# esp32-hanover-flipdot.net
KiCad netlist of a schematic drawn in EAGLE
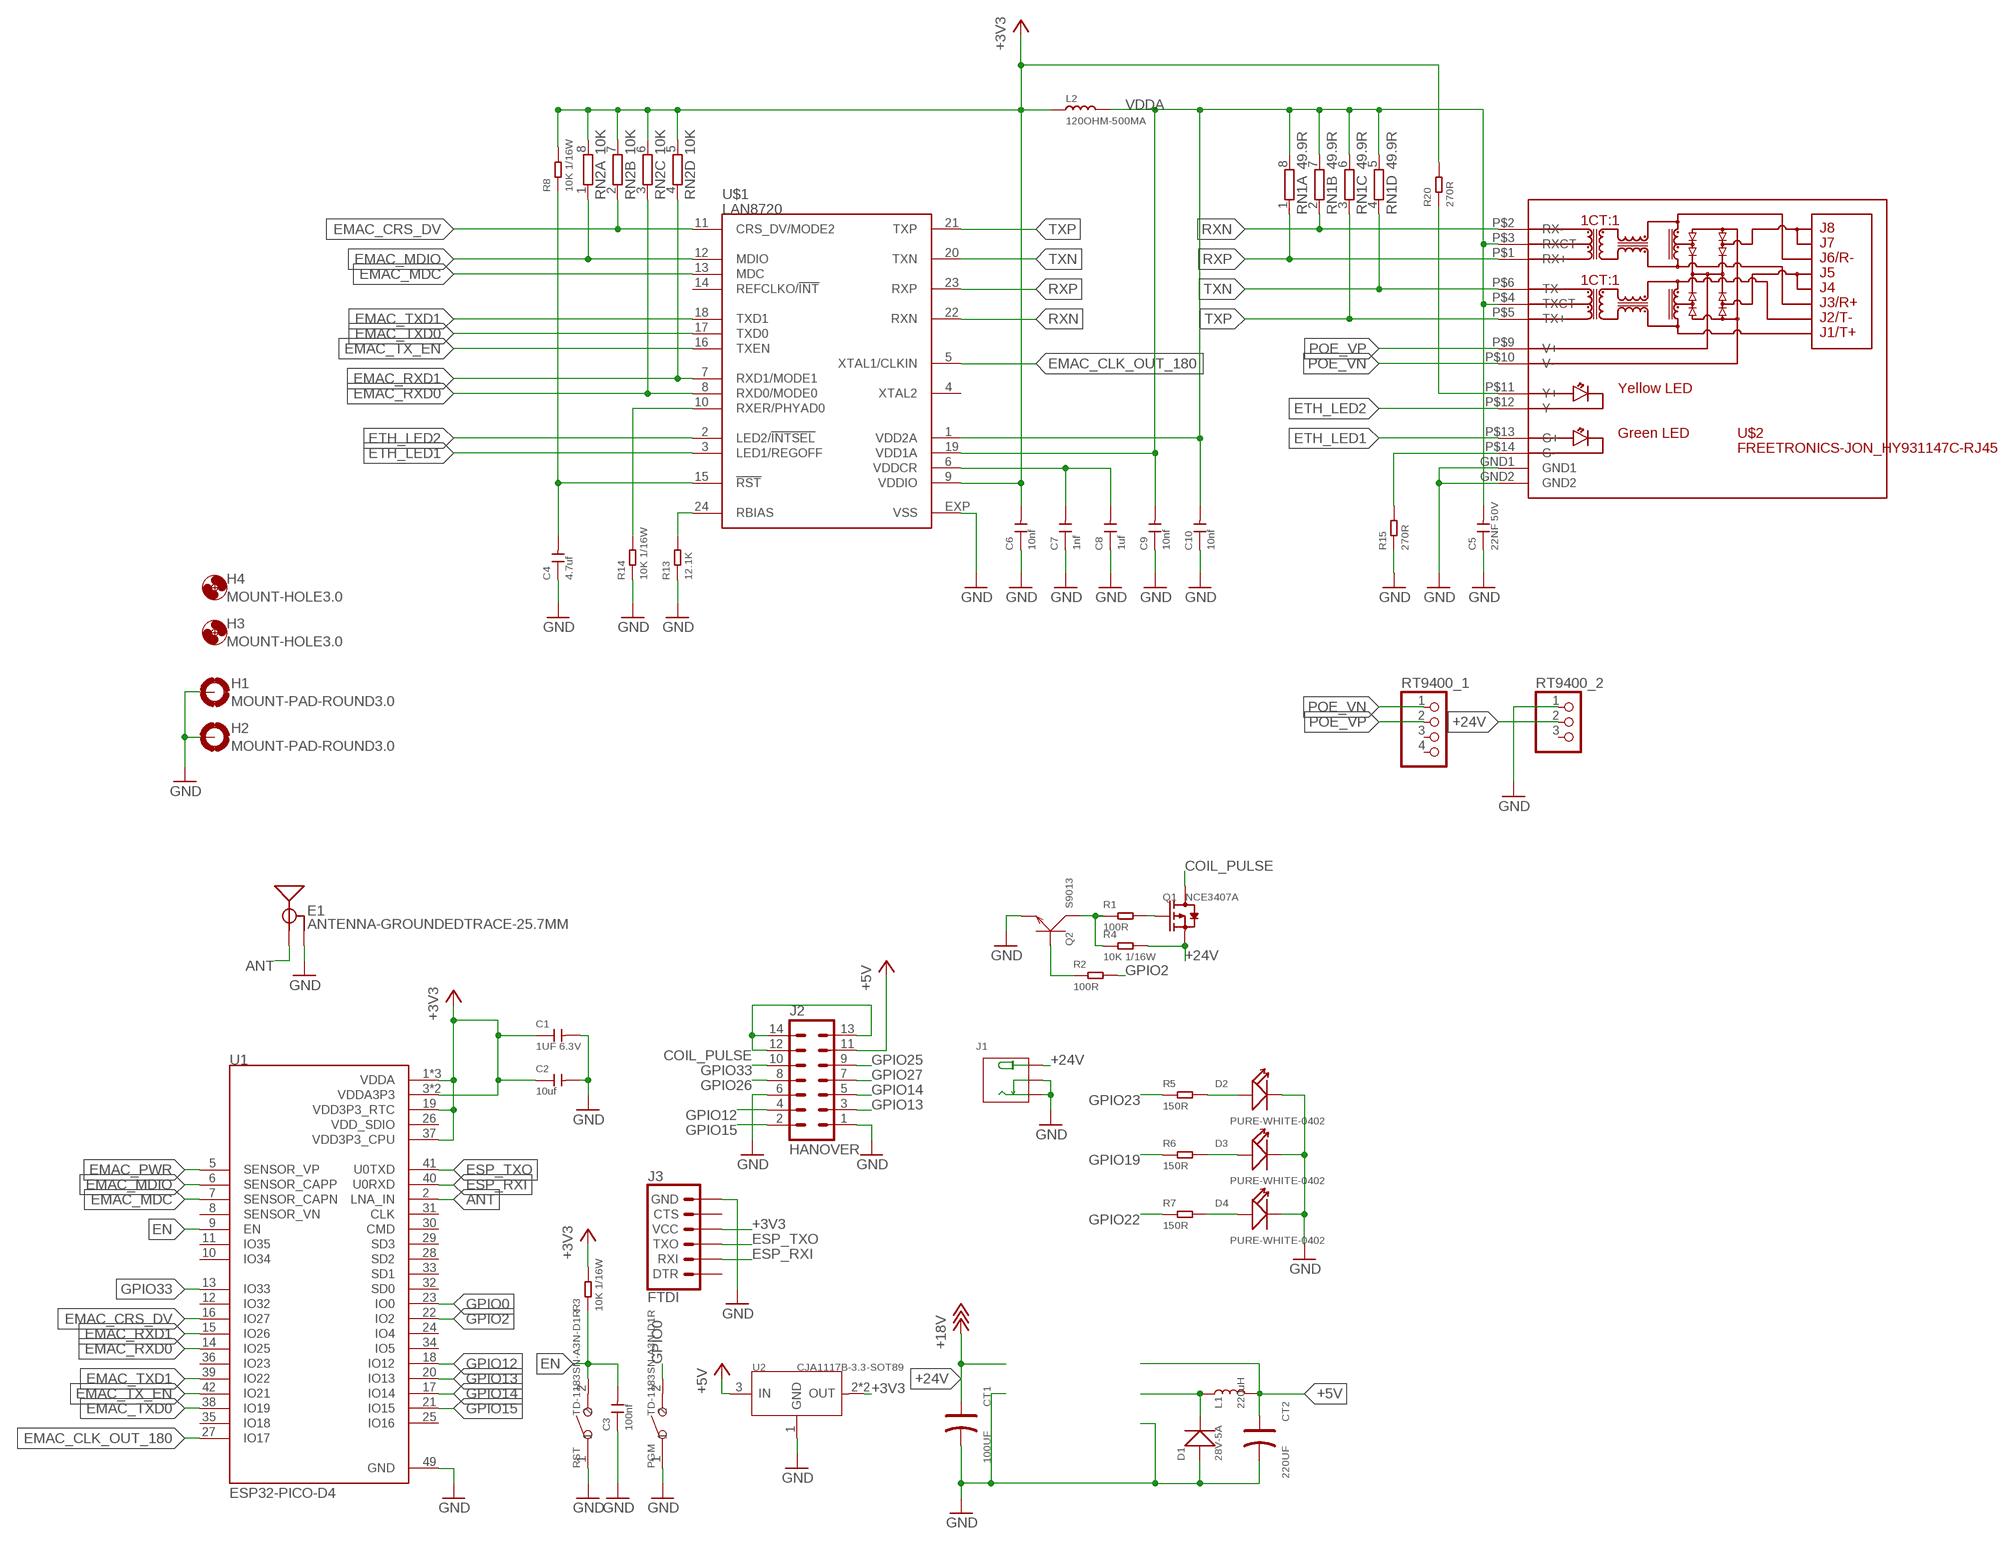
[diagram p0: schematic, sheet 1]

(export (version "E")
  (design (tool "Eeschema 10.0.6"))
  (components
    (comp (ref "C1")
      (value "1UF 6.3V")
      (footprint "eagle-import:C0402")
      (fields (field (name "MPN") "CC0402KRX5R5BB105"))
      (libsource (lib "eagle-import") (part "CERAMIC-1UF-6.3V-10%-X5R(0402)"))
    )
    (comp (ref "C2")
      (value "10uf")
      (footprint "eagle-import:C0402")
      (fields (field (name "MPN") "CC0402MRX5R5BB106"))
      (libsource (lib "eagle-import") (part "CERAMIC-10UF-6.3V-20%-X5R(0402)"))
    )
    (comp (ref "C3")
      (value "100nf")
      (footprint "eagle-import:C0402")
      (fields (field (name "MPN") "CC0402KRX7R8BB104"))
      (libsource (lib "eagle-import") (part "CERAMIC-100NF-25V-10%-X7R(0402)"))
    )
    (comp (ref "C4")
      (value "4.7uf")
      (footprint "eagle-import:C0402")
      (fields (field (name "MPN") "CC0402MRX5R5BB475"))
      (libsource (lib "eagle-import") (part "CERAMIC-4.7UF-6.3V-20%-X5R(0402)"))
    )
    (comp (ref "C5")
      (value "22NF 50V")
      (footprint "eagle-import:C0402")
      (fields (field (name "MPN") "CC0402KRX7R9BB223"))
      (libsource (lib "eagle-import") (part "CERAMIC-22NF-50V-10%-X7R(0402)"))
    )
    (comp (ref "C6")
      (value "10nf")
      (footprint "eagle-import:C0402")
      (fields (field (name "MPN") "CC0402KRX7R9BB103"))
      (libsource (lib "eagle-import") (part "CERAMIC-10NF-50V-10%-X7R(0402)"))
    )
    (comp (ref "C7")
      (value "1nf")
      (footprint "eagle-import:C0402")
      (fields (field (name "MPN") "CC0402KRX7R9BB102"))
      (libsource (lib "eagle-import") (part "CERAMIC-1NF-50V-10%-X7R(0402)"))
    )
    (comp (ref "C8")
      (value "1uf")
      (footprint "eagle-import:C0402")
      (fields (field (name "MPN") "CC0402KRX5R6BB105"))
      (libsource (lib "eagle-import") (part "CERAMIC-1UF-10V-10%-X5R(0402)"))
    )
    (comp (ref "C9")
      (value "10nf")
      (footprint "eagle-import:C0402")
      (fields (field (name "MPN") "CC0402KRX7R9BB103"))
      (libsource (lib "eagle-import") (part "CERAMIC-10NF-50V-10%-X7R(0402)"))
    )
    (comp (ref "C10")
      (value "10nf")
      (footprint "eagle-import:C0402")
      (fields (field (name "MPN") "CC0402KRX7R9BB103"))
      (libsource (lib "eagle-import") (part "CERAMIC-10NF-50V-10%-X7R(0402)"))
    )
    (comp (ref "CT1")
      (value "100UF")
      (footprint "eagle-import:ELECTRO-SMD-C-6MM")
      (fields (field (name "MPN") "CS1E221M-CRE77") (field (name "MPN_1") "302030000"))
      (libsource (lib "eagle-import") (part "ALUMINUM-SMD-220UF-16V(D6.3-H7.7MM)"))
    )
    (comp (ref "CT2")
      (value "220UF")
      (footprint "eagle-import:ELECTRO-SMD-C-6MM")
      (fields (field (name "MPN") "CS1E221M-CRE77"))
      (libsource (lib "eagle-import") (part "ALUMINUM-SMD-220UF-16V(D6.3-H7.7MM)"))
    )
    (comp (ref "D1")
      (value "28V-5A")
      (footprint "eagle-import:DO-214AA")
      (fields (field (name "MPN") "SS54B"))
      (libsource (lib "eagle-import") (part "SMD-DIODE-SCHOTTKY-28V-5A(DO-214AA)"))
    )
    (comp (ref "D2")
      (value "PURE-WHITE-0402")
      (footprint "eagle-import:LED-0402")
      (fields (field (name "MPN") "16-219A/T2D-AR2T1QY/3T"))
      (libsource (lib "eagle-import") (part "SMD-LED-YELLOW-DIFFUSED-PURE-WHITE(0402)"))
    )
    (comp (ref "D3")
      (value "PURE-WHITE-0402")
      (footprint "eagle-import:LED-0402")
      (fields (field (name "MPN") "16-219A/T2D-AR2T1QY/3T"))
      (libsource (lib "eagle-import") (part "SMD-LED-YELLOW-DIFFUSED-PURE-WHITE(0402)"))
    )
    (comp (ref "D4")
      (value "PURE-WHITE-0402")
      (footprint "eagle-import:LED-0402")
      (fields (field (name "MPN") "16-219A/T2D-AR2T1QY/3T"))
      (libsource (lib "eagle-import") (part "SMD-LED-YELLOW-DIFFUSED-PURE-WHITE(0402)"))
    )
    (comp (ref "E1")
      (value "ANTENNA-GROUNDEDTRACE-25.7MM")
      (footprint "eagle-import:TRACE_ANTENNA_2.4GHZ_25.7MM")
      (libsource (lib "eagle-import") (part "ANTENNA-GROUNDEDTRACE-25.7MM"))
    )
    (comp (ref "H1")
      (value "MOUNT-PAD-ROUND3.0")
      (footprint "eagle-import:3,0-PAD")
      (libsource (lib "eagle-import") (part "MOUNT-PAD-ROUND3.0"))
    )
    (comp (ref "H2")
      (value "MOUNT-PAD-ROUND3.0")
      (footprint "eagle-import:3,0-PAD")
      (libsource (lib "eagle-import") (part "MOUNT-PAD-ROUND3.0"))
    )
    (comp (ref "H3")
      (value "MOUNT-HOLE3.0")
      (footprint "eagle-import:3,0")
      (libsource (lib "eagle-import") (part "MOUNT-HOLE3.0"))
    )
    (comp (ref "H4")
      (value "MOUNT-HOLE3.0")
      (footprint "eagle-import:3,0")
      (libsource (lib "eagle-import") (part "MOUNT-HOLE3.0"))
    )
    (comp (ref "J1")
      (value "DC-005")
      (footprint "eagle-import:3P-L14.2_W11.0_H9.0MM")
      (libsource (lib "eagle-import") (part "JACK-DC-005'DC-005'"))
    )
    (comp (ref "J2")
      (value "HANOVER")
      (footprint "eagle-import:ML14")
      (libsource (lib "eagle-import") (part "ML14"))
    )
    (comp (ref "J3")
      (value "FTDI")
      (footprint "eagle-import:6_PIN_SERIAL_TARGET_SIDE_W_SILK")
      (libsource (lib "eagle-import") (part "6_PIN_SERIAL_TARGETSILK"))
    )
    (comp (ref "L1")
      (value "220uH")
      (footprint "eagle-import:CR54")
      (libsource (lib "eagle-import") (part "INDUCTOR-CR54-3.3UH"))
    )
    (comp (ref "L2")
      (value "120OHM-500MA")
      (footprint "eagle-import:L0603")
      (fields (field (name "MPN") "BLM18AG121SN1D"))
      (libsource (lib "eagle-import") (part "SMD-FERRITE-CHIP-120-OHM-500MA(0603)"))
    )
    (comp (ref "PGM")
      (value "TD-1183SN-A3N-D1R")
      (footprint "eagle-import:SW2-2.6-3.0X2.5X1.2+0.4MM")
      (fields (field (name "MPN") "B3U-1000P-2P-SMD"))
      (libsource (lib "eagle-import") (part "SMD-BUTTON(2P-3.0X2.5X1.2+0.4MM)-B3U-1000P-2P-SMD"))
    )
    (comp (ref "Q1")
      (value "NCE3407A")
      (footprint "eagle-import:SOT-23")
      (libsource (lib "eagle-import") (part "SMD-MOSFET-P-CH-VDC=30V-ID=4.3A-NCE3407A(SOT-23)"))
    )
    (comp (ref "Q2")
      (value "S9013")
      (footprint "eagle-import:SOT-23")
      (libsource (lib "eagle-import") (part "SMD-TRANSISTORS-NPN-25V-500MA-S9013(SOT-23)"))
    )
    (comp (ref "R1")
      (value "100R")
      (footprint "eagle-import:R0402")
      (fields (field (name "MPN") "RC0402JR-07100RL"))
      (libsource (lib "eagle-import") (part "SMD-RES-100R-5%-1/16W(0402)"))
    )
    (comp (ref "R2")
      (value "100R")
      (footprint "eagle-import:R0402")
      (fields (field (name "MPN") "RC0402JR-07100RL"))
      (libsource (lib "eagle-import") (part "SMD-RES-100R-5%-1/16W(0402)"))
    )
    (comp (ref "R3")
      (value "10K 1/16W")
      (footprint "eagle-import:R0402")
      (fields (field (name "MPN") "RC0402FR-0710KL"))
      (libsource (lib "eagle-import") (part "SMD-RES-10K-1%-1/16W(0402)"))
    )
    (comp (ref "R4")
      (value "10K 1/16W")
      (footprint "eagle-import:R0402")
      (fields (field (name "MPN") "RC0402FR-0710KL"))
      (libsource (lib "eagle-import") (part "SMD-RES-10K-1%-1/16W(0402)"))
    )
    (comp (ref "R5")
      (value "150R")
      (footprint "eagle-import:R0402")
      (fields (field (name "MPN") "RC0402JR-070RL") (field (name "MPN_1") "RC0402FR-07150RL"))
      (libsource (lib "eagle-import") (part "SMD-RES-150R-1%-1/16W(0402)"))
    )
    (comp (ref "R6")
      (value "150R")
      (footprint "eagle-import:R0402")
      (fields (field (name "MPN") "RC0402JR-070RL") (field (name "MPN_1") "RC0402FR-07150RL"))
      (libsource (lib "eagle-import") (part "SMD-RES-150R-1%-1/16W(0402)"))
    )
    (comp (ref "R7")
      (value "150R")
      (footprint "eagle-import:R0402")
      (fields (field (name "MPN") "RC0402JR-070RL") (field (name "MPN_1") "RC0402FR-07150RL"))
      (libsource (lib "eagle-import") (part "SMD-RES-150R-1%-1/16W(0402)"))
    )
    (comp (ref "R8")
      (value "10K 1/16W")
      (footprint "eagle-import:R0402")
      (fields (field (name "MPN") "RC0402FR-0710KL"))
      (libsource (lib "eagle-import") (part "SMD-RES-10K-1%-1/16W(0402)"))
    )
    (comp (ref "R13")
      (value "12.1K")
      (footprint "eagle-import:R0402")
      (fields (field (name "MPN") "RC0402JR-070RL"))
      (libsource (lib "eagle-import") (part "SMD-RES-12K-1%-1/16W(0402)"))
    )
    (comp (ref "R14")
      (value "10K 1/16W")
      (footprint "eagle-import:R0402")
      (fields (field (name "MPN") "RC0402FR-0710KL"))
      (libsource (lib "eagle-import") (part "SMD-RES-10K-1%-1/16W(0402)"))
    )
    (comp (ref "R15")
      (value "270R")
      (footprint "eagle-import:R0402")
      (fields (field (name "MPN") "RC0402JR-070RL"))
      (libsource (lib "eagle-import") (part "SMD-RES-270R-1%-1/16W(0402)"))
    )
    (comp (ref "R20")
      (value "270R")
      (footprint "eagle-import:R0402")
      (fields (field (name "MPN") "RC0402JR-070RL"))
      (libsource (lib "eagle-import") (part "SMD-RES-180R-1%-1/16W(0402)"))
    )
    (comp (ref "RN1")
      (value "49.9R")
      (footprint "eagle-import:YC124")
      (fields (field (name "MF") "Yageo") (field (name "MPN") "YC124-FR-0749R9L"))
      (libsource (lib "eagle-import") (part "4R-NYC124"))
    )
    (comp (ref "RN2")
      (value "10K")
      (footprint "eagle-import:YC124")
      (fields (field (name "MF") "Yageo") (field (name "MPN") "YC124-FR-0710KL"))
      (libsource (lib "eagle-import") (part "4R-NYC124"))
    )
    (comp (ref "RST")
      (value "TD-1183SN-A3N-D1R")
      (footprint "eagle-import:SW2-2.6-3.0X2.5X1.2+0.4MM")
      (fields (field (name "MPN") "B3U-1000P-2P-SMD"))
      (libsource (lib "eagle-import") (part "SMD-BUTTON(2P-3.0X2.5X1.2+0.4MM)-B3U-1000P-2P-SMD"))
    )
    (comp (ref "RT9400_1")
      (value "PINHD-1X4")
      (footprint "eagle-import:1X04")
      (libsource (lib "eagle-import") (part "PINHD-1X4"))
    )
    (comp (ref "RT9400_2")
      (value "PINHD-1X3")
      (footprint "eagle-import:1X03")
      (libsource (lib "eagle-import") (part "PINHD-1X3"))
    )
    (comp (ref "U$1")
      (value "LAN8720")
      (footprint "eagle-import:QFN24")
      (libsource (lib "eagle-import") (part "LAN8720"))
    )
    (comp (ref "U$2")
      (value "FREETRONICS-JON_HY931147C-RJ45")
      (footprint "eagle-import:FREETRONICS-JON_HY931147C")
      (libsource (lib "eagle-import") (part "FREETRONICS-JON_HY931147C-RJ45"))
    )
    (comp (ref "U1")
      (value "ESP32-PICO-D4")
      (footprint "eagle-import:PQFN50P700X700X104-49N")
      (fields (field (name "MF") "Espressif Systems"))
      (libsource (lib "eagle-import") (part "ESP32-PICO-D4"))
    )
    (comp (ref "U2")
      (value "CJA1117B-3.3-SOT89")
      (footprint "eagle-import:SOT-89")
      (fields (field (name "MPN") "CJA1117B-3.3"))
      (libsource (lib "eagle-import") (part "PMIC-CJA1117B-3.3(SOT-89)"))
    )
  )
  (nets
    (net (code "1") (name "+3V3") (class "Default")
      (node (ref "C1") (pin "1") (pinfunction "1_1") (pintype "passive"))
      (node (ref "C2") (pin "1") (pinfunction "1_1") (pintype "passive"))
      (node (ref "C6") (pin "2") (pinfunction "2_2") (pintype "passive"))
      (node (ref "J3") (pin "P$4") (pinfunction "VCC_P$4") (pintype "passive"))
      (node (ref "L2") (pin "1") (pinfunction "1_1") (pintype "passive"))
      (node (ref "R20") (pin "2") (pinfunction "2_2") (pintype "passive"))
      (node (ref "R3") (pin "2") (pinfunction "2_2") (pintype "passive"))
      (node (ref "R8") (pin "2") (pinfunction "2_2") (pintype "passive"))
      (node (ref "RN2") (pin "5") (pinfunction "2_5") (pintype "passive"))
      (node (ref "RN2") (pin "6") (pinfunction "2_6") (pintype "passive"))
      (node (ref "RN2") (pin "7") (pinfunction "2_7") (pintype "passive"))
      (node (ref "RN2") (pin "8") (pinfunction "2_8") (pintype "passive"))
      (node (ref "U$1") (pin "9") (pinfunction "VDDIO_9") (pintype "power_in"))
      (node (ref "U1") (pin "1") (pinfunction "VDDA_1") (pintype "power_in"))
      (node (ref "U1") (pin "19") (pinfunction "VDD3P3_RTC_19") (pintype "power_in"))
      (node (ref "U1") (pin "3") (pinfunction "VDDA3P3_3") (pintype "power_in"))
      (node (ref "U1") (pin "37") (pinfunction "VDD3P3_CPU_37") (pintype "power_in"))
      (node (ref "U1") (pin "4") (pinfunction "VDDA3P3_4") (pintype "power_in"))
      (node (ref "U1") (pin "43") (pinfunction "VDDA_43") (pintype "power_in"))
      (node (ref "U1") (pin "46") (pinfunction "VDDA_46") (pintype "power_in"))
      (node (ref "U2") (pin "2") (pinfunction "OUT_2") (pintype "bidirectional"))
      (node (ref "U2") (pin "4") (pinfunction "OUT_4") (pintype "bidirectional"))
    )
    (net (code "2") (name "+5V") (class "Default")
      (node (ref "CT2") (pin "+") (pinfunction "+_+") (pintype "passive"))
      (node (ref "J2") (pin "11") (pinfunction "11_11") (pintype "passive"))
      (node (ref "L1") (pin "P$2") (pinfunction "2_P$2") (pintype "passive"))
      (node (ref "U2") (pin "3") (pinfunction "IN_3") (pintype "bidirectional"))
    )
    (net (code "3") (name "+24V") (class "Default")
      (node (ref "CT1") (pin "+") (pinfunction "+_+") (pintype "passive"))
      (node (ref "J1") (pin "+B") (pinfunction "+_+B") (pintype "bidirectional"))
      (node (ref "J1") (pin "+T") (pinfunction "+_+T") (pintype "bidirectional"))
      (node (ref "Q1") (pin "2") (pinfunction "S_2") (pintype "passive"))
      (node (ref "R4") (pin "2") (pinfunction "2_2") (pintype "passive"))
      (node (ref "RT9400_2") (pin "2") (pinfunction "2_2") (pintype "passive"))
    )
    (net (code "4") (name "/COIL_PULSE") (class "Default")
      (node (ref "J2") (pin "12") (pinfunction "12_12") (pintype "passive"))
      (node (ref "J2") (pin "13") (pinfunction "13_13") (pintype "passive"))
      (node (ref "J2") (pin "14") (pinfunction "14_14") (pintype "passive"))
      (node (ref "Q1") (pin "3") (pinfunction "D_3") (pintype "passive"))
    )
    (net (code "5") (name "/GPIO19") (class "Default")
      (node (ref "R6") (pin "1") (pinfunction "1_1") (pintype "passive"))
    )
    (net (code "6") (name "/GPIO22") (class "Default")
      (node (ref "R7") (pin "1") (pinfunction "1_1") (pintype "passive"))
    )
    (net (code "7") (name "/GPIO23") (class "Default")
      (node (ref "R5") (pin "1") (pinfunction "1_1") (pintype "passive"))
    )
    (net (code "8") (name "/GPIO25") (class "Default")
      (node (ref "J2") (pin "9") (pinfunction "9_9") (pintype "passive"))
    )
    (net (code "9") (name "/GPIO26") (class "Default")
      (node (ref "J2") (pin "8") (pinfunction "8_8") (pintype "passive"))
    )
    (net (code "10") (name "/GPIO27") (class "Default")
      (node (ref "J2") (pin "7") (pinfunction "7_7") (pintype "passive"))
    )
    (net (code "11") (name "/VDDA") (class "Default")
      (node (ref "C10") (pin "2") (pinfunction "2_2") (pintype "passive"))
      (node (ref "C5") (pin "2") (pinfunction "2_2") (pintype "passive"))
      (node (ref "C9") (pin "2") (pinfunction "2_2") (pintype "passive"))
      (node (ref "L2") (pin "2") (pinfunction "2_2") (pintype "passive"))
      (node (ref "RN1") (pin "5") (pinfunction "2_5") (pintype "passive"))
      (node (ref "RN1") (pin "6") (pinfunction "2_6") (pintype "passive"))
      (node (ref "RN1") (pin "7") (pinfunction "2_7") (pintype "passive"))
      (node (ref "RN1") (pin "8") (pinfunction "2_8") (pintype "passive"))
      (node (ref "U$1") (pin "1") (pinfunction "VDD2A_1") (pintype "power_in"))
      (node (ref "U$1") (pin "19") (pinfunction "VDD1A_19") (pintype "power_in"))
      (node (ref "U$2") (pin "P$3") (pinfunction "RXCT_P$3") (pintype "bidirectional"))
      (node (ref "U$2") (pin "P$4") (pinfunction "TXCT_P$4") (pintype "bidirectional"))
    )
    (net (code "12") (name "/VDD_SDIO") (class "Default")
      (node (ref "U1") (pin "26") (pinfunction "VDD_SDIO_26") (pintype "power_in"))
    )
    (net (code "13") (name "ANT") (class "Default")
      (node (ref "E1") (pin "ANT") (pinfunction "SIGNAL_ANT") (pintype "bidirectional"))
      (node (ref "U1") (pin "2") (pinfunction "LNA_IN_2") (pintype "bidirectional"))
    )
    (net (code "14") (name "EMAC_CLK_OUT_180") (class "Default")
      (node (ref "U$1") (pin "5") (pinfunction "XTAL1/CLKIN_5") (pintype "bidirectional"))
      (node (ref "U1") (pin "27") (pinfunction "IO17_27") (pintype "bidirectional"))
    )
    (net (code "15") (name "EMAC_CRS_DV") (class "Default")
      (node (ref "RN2") (pin "2") (pinfunction "1_2") (pintype "passive"))
      (node (ref "U$1") (pin "11") (pinfunction "CRS_DV/MODE2_11") (pintype "bidirectional"))
      (node (ref "U1") (pin "16") (pinfunction "IO27_16") (pintype "bidirectional"))
    )
    (net (code "16") (name "EMAC_MDC") (class "Default")
      (node (ref "U$1") (pin "13") (pinfunction "MDC_13") (pintype "bidirectional"))
      (node (ref "U1") (pin "7") (pinfunction "SENSOR_CAPN_7") (pintype "input"))
    )
    (net (code "17") (name "EMAC_MDIO") (class "Default")
      (node (ref "RN2") (pin "1") (pinfunction "1_1") (pintype "passive"))
      (node (ref "U$1") (pin "12") (pinfunction "MDIO_12") (pintype "bidirectional"))
      (node (ref "U1") (pin "6") (pinfunction "SENSOR_CAPP_6") (pintype "input"))
    )
    (net (code "18") (name "EMAC_PWR") (class "Default")
      (node (ref "U1") (pin "5") (pinfunction "SENSOR_VP_5") (pintype "input"))
    )
    (net (code "19") (name "EMAC_RXD0") (class "Default")
      (node (ref "RN2") (pin "3") (pinfunction "1_3") (pintype "passive"))
      (node (ref "U$1") (pin "8") (pinfunction "RXD0/MODE0_8") (pintype "bidirectional"))
      (node (ref "U1") (pin "14") (pinfunction "IO25_14") (pintype "bidirectional"))
    )
    (net (code "20") (name "EMAC_RXD1") (class "Default")
      (node (ref "RN2") (pin "4") (pinfunction "1_4") (pintype "passive"))
      (node (ref "U$1") (pin "7") (pinfunction "RXD1/MODE1_7") (pintype "bidirectional"))
      (node (ref "U1") (pin "15") (pinfunction "IO26_15") (pintype "bidirectional"))
    )
    (net (code "21") (name "EMAC_TXD0") (class "Default")
      (node (ref "U$1") (pin "17") (pinfunction "TXD0_17") (pintype "bidirectional"))
      (node (ref "U1") (pin "38") (pinfunction "IO19_38") (pintype "bidirectional"))
    )
    (net (code "22") (name "EMAC_TXD1") (class "Default")
      (node (ref "U$1") (pin "18") (pinfunction "TXD1_18") (pintype "bidirectional"))
      (node (ref "U1") (pin "39") (pinfunction "IO22_39") (pintype "bidirectional"))
    )
    (net (code "23") (name "EMAC_TX_EN") (class "Default")
      (node (ref "U$1") (pin "16") (pinfunction "TXEN_16") (pintype "bidirectional"))
      (node (ref "U1") (pin "42") (pinfunction "IO21_42") (pintype "bidirectional"))
    )
    (net (code "24") (name "EN") (class "Default")
      (node (ref "C3") (pin "2") (pinfunction "2_2") (pintype "passive"))
      (node (ref "R3") (pin "1") (pinfunction "1_1") (pintype "passive"))
      (node (ref "RST") (pin "2") (pinfunction "2_2") (pintype "bidirectional"))
      (node (ref "U1") (pin "9") (pinfunction "EN_9") (pintype "input"))
    )
    (net (code "25") (name "ESP_RXI") (class "Default")
      (node (ref "J3") (pin "P$3") (pinfunction "RXI_P$3") (pintype "passive"))
      (node (ref "U1") (pin "40") (pinfunction "U0RXD_40") (pintype "bidirectional"))
    )
    (net (code "26") (name "ESP_TXO") (class "Default")
      (node (ref "J3") (pin "P$2") (pinfunction "TXO_P$2") (pintype "passive"))
      (node (ref "U1") (pin "41") (pinfunction "U0TXD_41") (pintype "bidirectional"))
    )
    (net (code "27") (name "ETH_LED1") (class "Default")
      (node (ref "U$1") (pin "3") (pinfunction "LED1/REGOFF_3") (pintype "bidirectional"))
      (node (ref "U$2") (pin "P$13") (pinfunction "G+_P$13") (pintype "bidirectional"))
    )
    (net (code "28") (name "ETH_LED2") (class "Default")
      (node (ref "U$1") (pin "2") (pinfunction "LED2/~{INTSEL}_2") (pintype "bidirectional"))
      (node (ref "U$2") (pin "P$12") (pinfunction "Y-_P$12") (pintype "bidirectional"))
    )
    (net (code "29") (name "GND") (class "Default")
      (node (ref "C1") (pin "2") (pinfunction "2_2") (pintype "passive"))
      (node (ref "C10") (pin "1") (pinfunction "1_1") (pintype "passive"))
      (node (ref "C2") (pin "2") (pinfunction "2_2") (pintype "passive"))
      (node (ref "C3") (pin "1") (pinfunction "1_1") (pintype "passive"))
      (node (ref "C4") (pin "1") (pinfunction "1_1") (pintype "passive"))
      (node (ref "C5") (pin "1") (pinfunction "1_1") (pintype "passive"))
      (node (ref "C6") (pin "1") (pinfunction "1_1") (pintype "passive"))
      (node (ref "C7") (pin "1") (pinfunction "1_1") (pintype "passive"))
      (node (ref "C8") (pin "1") (pinfunction "1_1") (pintype "passive"))
      (node (ref "C9") (pin "1") (pinfunction "1_1") (pintype "passive"))
      (node (ref "CT1") (pin "-") (pinfunction "-_-") (pintype "passive"))
      (node (ref "CT2") (pin "-") (pinfunction "-_-") (pintype "passive"))
      (node (ref "D1") (pin "+") (pinfunction "+_+") (pintype "passive"))
      (node (ref "D2") (pin "-") (pinfunction "-_-") (pintype "passive"))
      (node (ref "D3") (pin "-") (pinfunction "-_-") (pintype "passive"))
      (node (ref "D4") (pin "-") (pinfunction "-_-") (pintype "passive"))
      (node (ref "E1") (pin "GND") (pinfunction "GND_GND") (pintype "bidirectional"))
      (node (ref "E1") (pin "GND2") (pinfunction "GND_GND2") (pintype "bidirectional"))
      (node (ref "H1") (pin "B3,0") (pinfunction "MOUNT_B3,0") (pintype "passive"))
      (node (ref "H2") (pin "B3,0") (pinfunction "MOUNT_B3,0") (pintype "passive"))
      (node (ref "J1") (pin "-1B") (pinfunction "-_-1B") (pintype "bidirectional"))
      (node (ref "J1") (pin "-1T") (pinfunction "-_-1T") (pintype "bidirectional"))
      (node (ref "J1") (pin "-2B") (pinfunction "CDN_-2B") (pintype "bidirectional"))
      (node (ref "J1") (pin "-2T") (pinfunction "CDN_-2T") (pintype "bidirectional"))
      (node (ref "J2") (pin "1") (pinfunction "1_1") (pintype "passive"))
      (node (ref "J2") (pin "6") (pinfunction "6_6") (pintype "passive"))
      (node (ref "J3") (pin "P$6") (pinfunction "GND_P$6") (pintype "passive"))
      (node (ref "PGM") (pin "1") (pinfunction "1_1") (pintype "bidirectional"))
      (node (ref "Q2") (pin "2") (pinfunction "E_2") (pintype "passive"))
      (node (ref "R13") (pin "1") (pinfunction "1_1") (pintype "passive"))
      (node (ref "R14") (pin "1") (pinfunction "1_1") (pintype "passive"))
      (node (ref "R15") (pin "1") (pinfunction "1_1") (pintype "passive"))
      (node (ref "RST") (pin "1") (pinfunction "1_1") (pintype "bidirectional"))
      (node (ref "RT9400_2") (pin "1") (pinfunction "1_1") (pintype "passive"))
      (node (ref "U$1") (pin "EXP") (pinfunction "VSS_EXP") (pintype "power_in"))
      (node (ref "U$2") (pin "GND1") (pinfunction "GND1_GND1") (pintype "bidirectional"))
      (node (ref "U$2") (pin "GND2") (pinfunction "GND2_GND2") (pintype "bidirectional"))
      (node (ref "U1") (pin "49") (pinfunction "GND_49") (pintype "power_in"))
      (node (ref "U2") (pin "1") (pinfunction "GND_1") (pintype "bidirectional"))
    )
    (net (code "30") (name "GPIO0") (class "Default")
      (node (ref "PGM") (pin "2") (pinfunction "2_2") (pintype "bidirectional"))
      (node (ref "U1") (pin "23") (pinfunction "IO0_23") (pintype "bidirectional"))
    )
    (net (code "31") (name "GPIO2") (class "Default")
      (node (ref "R2") (pin "2") (pinfunction "2_2") (pintype "passive"))
      (node (ref "U1") (pin "22") (pinfunction "IO2_22") (pintype "bidirectional"))
    )
    (net (code "32") (name "GPIO12") (class "Default")
      (node (ref "J2") (pin "4") (pinfunction "4_4") (pintype "passive"))
      (node (ref "U1") (pin "18") (pinfunction "IO12_18") (pintype "bidirectional"))
    )
    (net (code "33") (name "GPIO13") (class "Default")
      (node (ref "J2") (pin "3") (pinfunction "3_3") (pintype "passive"))
      (node (ref "U1") (pin "20") (pinfunction "IO13_20") (pintype "bidirectional"))
    )
    (net (code "34") (name "GPIO14") (class "Default")
      (node (ref "J2") (pin "5") (pinfunction "5_5") (pintype "passive"))
      (node (ref "U1") (pin "17") (pinfunction "IO14_17") (pintype "bidirectional"))
    )
    (net (code "35") (name "GPIO15") (class "Default")
      (node (ref "J2") (pin "2") (pinfunction "2_2") (pintype "passive"))
      (node (ref "U1") (pin "21") (pinfunction "IO15_21") (pintype "bidirectional"))
    )
    (net (code "36") (name "GPIO33") (class "Default")
      (node (ref "J2") (pin "10") (pinfunction "10_10") (pintype "passive"))
      (node (ref "U1") (pin "13") (pinfunction "IO33_13") (pintype "bidirectional"))
    )
    (net (code "37") (name "Net-(D2-Pad+)") (class "Default")
      (node (ref "D2") (pin "+") (pinfunction "+_+") (pintype "passive"))
      (node (ref "R5") (pin "2") (pinfunction "2_2") (pintype "passive"))
    )
    (net (code "38") (name "Net-(D3-Pad+)") (class "Default")
      (node (ref "D3") (pin "+") (pinfunction "+_+") (pintype "passive"))
      (node (ref "R6") (pin "2") (pinfunction "2_2") (pintype "passive"))
    )
    (net (code "39") (name "Net-(D4-Pad+)") (class "Default")
      (node (ref "D4") (pin "+") (pinfunction "+_+") (pintype "passive"))
      (node (ref "R7") (pin "2") (pinfunction "2_2") (pintype "passive"))
    )
    (net (code "40") (name "Net-(L1-1)") (class "Default")
      (node (ref "D1") (pin "-") (pinfunction "-_-") (pintype "passive"))
      (node (ref "L1") (pin "P$1") (pinfunction "1_P$1") (pintype "passive"))
    )
    (net (code "41") (name "Net-(Q1-G)") (class "Default")
      (node (ref "Q1") (pin "1") (pinfunction "G_1") (pintype "passive"))
      (node (ref "R1") (pin "2") (pinfunction "2_2") (pintype "passive"))
    )
    (net (code "42") (name "Net-(Q2-B)") (class "Default")
      (node (ref "Q2") (pin "1") (pinfunction "B_1") (pintype "passive"))
      (node (ref "R2") (pin "1") (pinfunction "1_1") (pintype "passive"))
    )
    (net (code "43") (name "Net-(Q2-C)") (class "Default")
      (node (ref "Q2") (pin "3") (pinfunction "C_3") (pintype "passive"))
      (node (ref "R1") (pin "1") (pinfunction "1_1") (pintype "passive"))
      (node (ref "R4") (pin "1") (pinfunction "1_1") (pintype "passive"))
    )
    (net (code "44") (name "Net-(U$1-RBIAS)") (class "Default")
      (node (ref "R13") (pin "2") (pinfunction "2_2") (pintype "passive"))
      (node (ref "U$1") (pin "24") (pinfunction "RBIAS_24") (pintype "bidirectional"))
    )
    (net (code "45") (name "Net-(U$1-RXER{slash}PHYAD0)") (class "Default")
      (node (ref "R14") (pin "2") (pinfunction "2_2") (pintype "passive"))
      (node (ref "U$1") (pin "10") (pinfunction "RXER/PHYAD0_10") (pintype "bidirectional"))
    )
    (net (code "46") (name "Net-(U$1-VDDCR)") (class "Default")
      (node (ref "C7") (pin "2") (pinfunction "2_2") (pintype "passive"))
      (node (ref "C8") (pin "2") (pinfunction "2_2") (pintype "passive"))
      (node (ref "U$1") (pin "6") (pinfunction "VDDCR_6") (pintype "power_in"))
    )
    (net (code "47") (name "Net-(U$1-~{RST})") (class "Default")
      (node (ref "C4") (pin "2") (pinfunction "2_2") (pintype "passive"))
      (node (ref "R8") (pin "1") (pinfunction "1_1") (pintype "passive"))
      (node (ref "U$1") (pin "15") (pinfunction "~{RST}_15") (pintype "bidirectional"))
    )
    (net (code "48") (name "Net-(U$2-G-)") (class "Default")
      (node (ref "R15") (pin "2") (pinfunction "2_2") (pintype "passive"))
      (node (ref "U$2") (pin "P$14") (pinfunction "G-_P$14") (pintype "bidirectional"))
    )
    (net (code "49") (name "Net-(U$2-Y+)") (class "Default")
      (node (ref "R20") (pin "1") (pinfunction "1_1") (pintype "passive"))
      (node (ref "U$2") (pin "P$11") (pinfunction "Y+_P$11") (pintype "bidirectional"))
    )
    (net (code "50") (name "POE_VN") (class "Default")
      (node (ref "RT9400_1") (pin "1") (pinfunction "1_1") (pintype "passive"))
      (node (ref "U$2") (pin "P$10") (pinfunction "V-_P$10") (pintype "bidirectional"))
    )
    (net (code "51") (name "POE_VP") (class "Default")
      (node (ref "RT9400_1") (pin "2") (pinfunction "2_2") (pintype "passive"))
      (node (ref "U$2") (pin "P$9") (pinfunction "V+_P$9") (pintype "bidirectional"))
    )
    (net (code "52") (name "RXN") (class "Default")
      (node (ref "RN1") (pin "2") (pinfunction "1_2") (pintype "passive"))
      (node (ref "U$1") (pin "22") (pinfunction "RXN_22") (pintype "bidirectional"))
      (node (ref "U$2") (pin "P$2") (pinfunction "RX-_P$2") (pintype "bidirectional"))
    )
    (net (code "53") (name "RXP") (class "Default")
      (node (ref "RN1") (pin "1") (pinfunction "1_1") (pintype "passive"))
      (node (ref "U$1") (pin "23") (pinfunction "RXP_23") (pintype "bidirectional"))
      (node (ref "U$2") (pin "P$1") (pinfunction "RX+_P$1") (pintype "bidirectional"))
    )
    (net (code "54") (name "TXN") (class "Default")
      (node (ref "RN1") (pin "4") (pinfunction "1_4") (pintype "passive"))
      (node (ref "U$1") (pin "20") (pinfunction "TXN_20") (pintype "bidirectional"))
      (node (ref "U$2") (pin "P$6") (pinfunction "TX-_P$6") (pintype "bidirectional"))
    )
    (net (code "55") (name "TXP") (class "Default")
      (node (ref "RN1") (pin "3") (pinfunction "1_3") (pintype "passive"))
      (node (ref "U$1") (pin "21") (pinfunction "TXP_21") (pintype "bidirectional"))
      (node (ref "U$2") (pin "P$5") (pinfunction "TX+_P$5") (pintype "bidirectional"))
    )
    (net (code "56") (name "unconnected-(J3-CTS-PadP$5)") (class "Default")
      (node (ref "J3") (pin "P$5") (pinfunction "CTS_P$5") (pintype "passive"))
    )
    (net (code "57") (name "unconnected-(J3-DTR-PadP$1)") (class "Default")
      (node (ref "J3") (pin "P$1") (pinfunction "DTR_P$1") (pintype "passive"))
    )
    (net (code "58") (name "unconnected-(RT9400_1-Pad3)") (class "Default")
      (node (ref "RT9400_1") (pin "3") (pinfunction "3_3") (pintype "passive"))
    )
    (net (code "59") (name "unconnected-(RT9400_1-Pad4)") (class "Default")
      (node (ref "RT9400_1") (pin "4") (pinfunction "4_4") (pintype "passive"))
    )
    (net (code "60") (name "unconnected-(RT9400_2-Pad3)") (class "Default")
      (node (ref "RT9400_2") (pin "3") (pinfunction "3_3") (pintype "passive"))
    )
    (net (code "61") (name "unconnected-(U$1-REFCLKO{slash}~{INT}-Pad14)") (class "Default")
      (node (ref "U$1") (pin "14") (pinfunction "REFCLKO/~{INT}_14") (pintype "bidirectional"))
    )
    (net (code "62") (name "unconnected-(U$1-XTAL2-Pad4)") (class "Default")
      (node (ref "U$1") (pin "4") (pinfunction "XTAL2_4") (pintype "bidirectional"))
    )
    (net (code "63") (name "unconnected-(U1-CLK-Pad31)") (class "Default")
      (node (ref "U1") (pin "31") (pinfunction "CLK_31") (pintype "bidirectional"))
    )
    (net (code "64") (name "unconnected-(U1-CMD-Pad30)") (class "Default")
      (node (ref "U1") (pin "30") (pinfunction "CMD_30") (pintype "bidirectional"))
    )
    (net (code "65") (name "unconnected-(U1-IO4-Pad24)") (class "Default")
      (node (ref "U1") (pin "24") (pinfunction "IO4_24") (pintype "bidirectional"))
    )
    (net (code "66") (name "unconnected-(U1-IO5-Pad34)") (class "Default")
      (node (ref "U1") (pin "34") (pinfunction "IO5_34") (pintype "bidirectional"))
    )
    (net (code "67") (name "unconnected-(U1-IO16-Pad25)") (class "Default")
      (node (ref "U1") (pin "25") (pinfunction "IO16_25") (pintype "bidirectional"))
    )
    (net (code "68") (name "unconnected-(U1-IO18-Pad35)") (class "Default")
      (node (ref "U1") (pin "35") (pinfunction "IO18_35") (pintype "bidirectional"))
    )
    (net (code "69") (name "unconnected-(U1-IO23-Pad36)") (class "Default")
      (node (ref "U1") (pin "36") (pinfunction "IO23_36") (pintype "bidirectional"))
    )
    (net (code "70") (name "unconnected-(U1-IO32-Pad12)") (class "Default")
      (node (ref "U1") (pin "12") (pinfunction "IO32_12") (pintype "bidirectional"))
    )
    (net (code "71") (name "unconnected-(U1-IO34-Pad10)") (class "Default")
      (node (ref "U1") (pin "10") (pinfunction "IO34_10") (pintype "input"))
    )
    (net (code "72") (name "unconnected-(U1-IO35-Pad11)") (class "Default")
      (node (ref "U1") (pin "11") (pinfunction "IO35_11") (pintype "input"))
    )
    (net (code "73") (name "unconnected-(U1-SD0-Pad32)") (class "Default")
      (node (ref "U1") (pin "32") (pinfunction "SD0_32") (pintype "bidirectional"))
    )
    (net (code "74") (name "unconnected-(U1-SD1-Pad33)") (class "Default")
      (node (ref "U1") (pin "33") (pinfunction "SD1_33") (pintype "bidirectional"))
    )
    (net (code "75") (name "unconnected-(U1-SD2-Pad28)") (class "Default")
      (node (ref "U1") (pin "28") (pinfunction "SD2_28") (pintype "bidirectional"))
    )
    (net (code "76") (name "unconnected-(U1-SD3-Pad29)") (class "Default")
      (node (ref "U1") (pin "29") (pinfunction "SD3_29") (pintype "bidirectional"))
    )
    (net (code "77") (name "unconnected-(U1-SENSOR_VN-Pad8)") (class "Default")
      (node (ref "U1") (pin "8") (pinfunction "SENSOR_VN_8") (pintype "input"))
    )
  )
)
